# 74HC595.net
KiCad netlist of a schematic drawn in Altium Designer
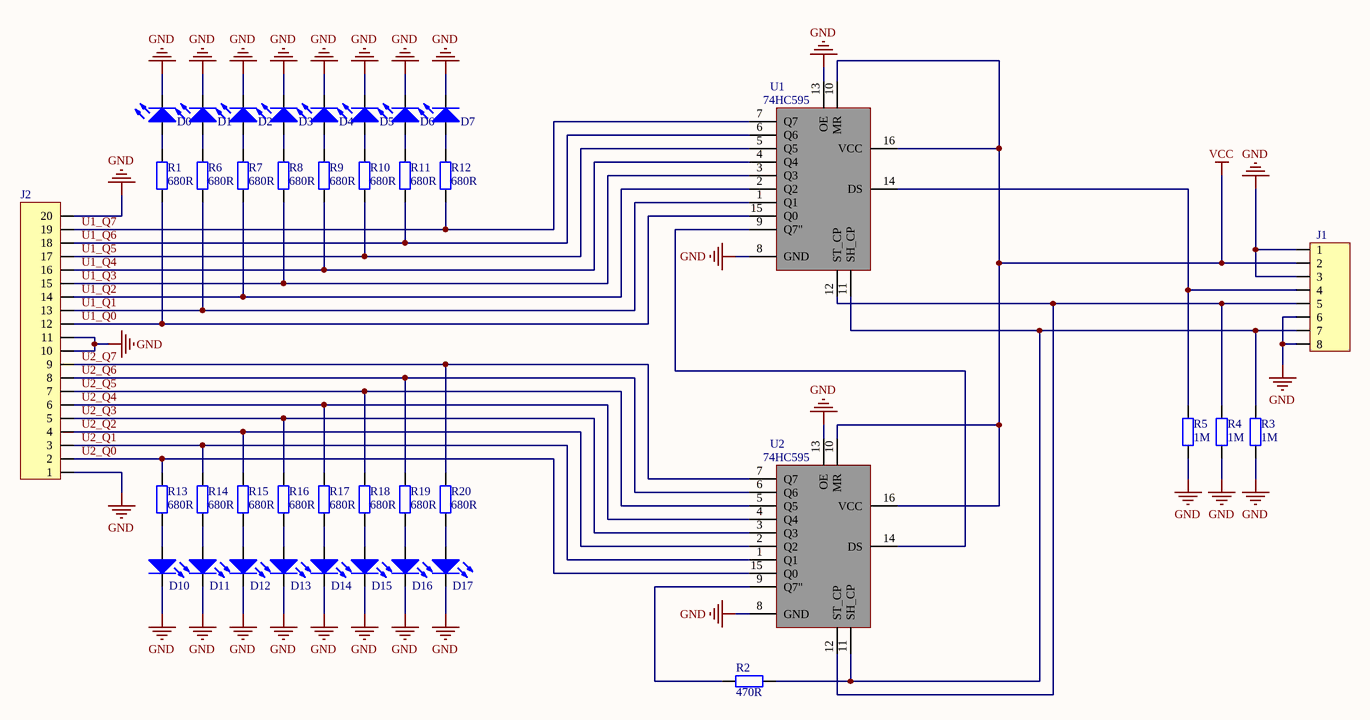
[diagram p0: 74HC595.SchDoc]

(export (version "E")
  (design (tool "Eeschema 10.0.6"))
  (components
    (comp (ref "D0")
      (value "LED0")
      (footprint "USER:1206LED")
      (description "LED灯")
      (fields (field (name "PUBLISHER") "Altium Limited"))
      (libsource (lib "USER") (part "LED0"))
    )
    (comp (ref "D1")
      (value "LED0")
      (footprint "USER:1206LED")
      (description "LED灯")
      (fields (field (name "PUBLISHER") "Altium Limited"))
      (libsource (lib "USER") (part "LED0"))
    )
    (comp (ref "D2")
      (value "LED0")
      (footprint "USER:1206LED")
      (description "LED灯")
      (fields (field (name "PUBLISHER") "Altium Limited"))
      (libsource (lib "USER") (part "LED0"))
    )
    (comp (ref "D3")
      (value "LED0")
      (footprint "USER:1206LED")
      (description "LED灯")
      (fields (field (name "PUBLISHER") "Altium Limited"))
      (libsource (lib "USER") (part "LED0"))
    )
    (comp (ref "D4")
      (value "LED0")
      (footprint "USER:1206LED")
      (description "LED灯")
      (fields (field (name "PUBLISHER") "Altium Limited"))
      (libsource (lib "USER") (part "LED0"))
    )
    (comp (ref "D5")
      (value "LED0")
      (footprint "USER:1206LED")
      (description "LED灯")
      (fields (field (name "PUBLISHER") "Altium Limited"))
      (libsource (lib "USER") (part "LED0"))
    )
    (comp (ref "D6")
      (value "LED0")
      (footprint "USER:1206LED")
      (description "LED灯")
      (fields (field (name "PUBLISHER") "Altium Limited"))
      (libsource (lib "USER") (part "LED0"))
    )
    (comp (ref "D7")
      (value "LED0")
      (footprint "USER:1206LED")
      (description "LED灯")
      (fields (field (name "PUBLISHER") "Altium Limited"))
      (libsource (lib "USER") (part "LED0"))
    )
    (comp (ref "D10")
      (value "LED0")
      (footprint "USER:1206LED")
      (description "LED灯")
      (fields (field (name "PUBLISHER") "Altium Limited"))
      (libsource (lib "USER") (part "LED0"))
    )
    (comp (ref "D11")
      (value "LED0")
      (footprint "USER:1206LED")
      (description "LED灯")
      (fields (field (name "PUBLISHER") "Altium Limited"))
      (libsource (lib "USER") (part "LED0"))
    )
    (comp (ref "D12")
      (value "LED0")
      (footprint "USER:1206LED")
      (description "LED灯")
      (fields (field (name "PUBLISHER") "Altium Limited"))
      (libsource (lib "USER") (part "LED0"))
    )
    (comp (ref "D13")
      (value "LED0")
      (footprint "USER:1206LED")
      (description "LED灯")
      (fields (field (name "PUBLISHER") "Altium Limited"))
      (libsource (lib "USER") (part "LED0"))
    )
    (comp (ref "D14")
      (value "LED0")
      (footprint "USER:1206LED")
      (description "LED灯")
      (fields (field (name "PUBLISHER") "Altium Limited"))
      (libsource (lib "USER") (part "LED0"))
    )
    (comp (ref "D15")
      (value "LED0")
      (footprint "USER:1206LED")
      (description "LED灯")
      (fields (field (name "PUBLISHER") "Altium Limited"))
      (libsource (lib "USER") (part "LED0"))
    )
    (comp (ref "D16")
      (value "LED0")
      (footprint "USER:1206LED")
      (description "LED灯")
      (fields (field (name "PUBLISHER") "Altium Limited"))
      (libsource (lib "USER") (part "LED0"))
    )
    (comp (ref "D17")
      (value "LED0")
      (footprint "USER:1206LED")
      (description "LED灯")
      (fields (field (name "PUBLISHER") "Altium Limited"))
      (libsource (lib "USER") (part "LED0"))
    )
    (comp (ref "J1")
      (value "Header8")
      (footprint "user:8P-2.54-H")
      (description "8PIN插座")
      (libsource (lib "USER") (part "Header8"))
    )
    (comp (ref "J2")
      (value "Header20")
      (footprint "USER:20P-2.54-H")
      (description "20PIN插座")
      (libsource (lib "USER") (part "Header20"))
    )
    (comp (ref "R1")
      (value "680R")
      (footprint "0805R_M")
      (description "电阻")
      (fields (field (name "PUBLISHER") "Altium Limited"))
      (libsource (lib "USER") (part "Res"))
    )
    (comp (ref "R2")
      (value "470R")
      (footprint "0805R_M")
      (description "电阻")
      (fields (field (name "PUBLISHER") "Altium Limited"))
      (libsource (lib "") (part "Res_1"))
    )
    (comp (ref "R3")
      (value "1M")
      (footprint "0805R_M")
      (description "电阻")
      (fields (field (name "PUBLISHER") "Altium Limited"))
      (libsource (lib "USER") (part "Res"))
    )
    (comp (ref "R4")
      (value "1M")
      (footprint "0805R_M")
      (description "电阻")
      (fields (field (name "PUBLISHER") "Altium Limited"))
      (libsource (lib "USER") (part "Res"))
    )
    (comp (ref "R5")
      (value "1M")
      (footprint "0805R_M")
      (description "电阻")
      (fields (field (name "PUBLISHER") "Altium Limited"))
      (libsource (lib "USER") (part "Res"))
    )
    (comp (ref "R6")
      (value "680R")
      (footprint "0805R_M")
      (description "电阻")
      (fields (field (name "PUBLISHER") "Altium Limited"))
      (libsource (lib "USER") (part "Res"))
    )
    (comp (ref "R7")
      (value "680R")
      (footprint "0805R_M")
      (description "电阻")
      (fields (field (name "PUBLISHER") "Altium Limited"))
      (libsource (lib "USER") (part "Res"))
    )
    (comp (ref "R8")
      (value "680R")
      (footprint "0805R_M")
      (description "电阻")
      (fields (field (name "PUBLISHER") "Altium Limited"))
      (libsource (lib "USER") (part "Res"))
    )
    (comp (ref "R9")
      (value "680R")
      (footprint "0805R_M")
      (description "电阻")
      (fields (field (name "PUBLISHER") "Altium Limited"))
      (libsource (lib "USER") (part "Res"))
    )
    (comp (ref "R10")
      (value "680R")
      (footprint "0805R_M")
      (description "电阻")
      (fields (field (name "PUBLISHER") "Altium Limited"))
      (libsource (lib "USER") (part "Res"))
    )
    (comp (ref "R11")
      (value "680R")
      (footprint "0805R_M")
      (description "电阻")
      (fields (field (name "PUBLISHER") "Altium Limited"))
      (libsource (lib "USER") (part "Res"))
    )
    (comp (ref "R12")
      (value "680R")
      (footprint "0805R_M")
      (description "电阻")
      (fields (field (name "PUBLISHER") "Altium Limited"))
      (libsource (lib "USER") (part "Res"))
    )
    (comp (ref "R13")
      (value "680R")
      (footprint "0805R_M")
      (description "电阻")
      (fields (field (name "PUBLISHER") "Altium Limited"))
      (libsource (lib "USER") (part "Res"))
    )
    (comp (ref "R14")
      (value "680R")
      (footprint "0805R_M")
      (description "电阻")
      (fields (field (name "PUBLISHER") "Altium Limited"))
      (libsource (lib "USER") (part "Res"))
    )
    (comp (ref "R15")
      (value "680R")
      (footprint "0805R_M")
      (description "电阻")
      (fields (field (name "PUBLISHER") "Altium Limited"))
      (libsource (lib "USER") (part "Res"))
    )
    (comp (ref "R16")
      (value "680R")
      (footprint "0805R_M")
      (description "电阻")
      (fields (field (name "PUBLISHER") "Altium Limited"))
      (libsource (lib "USER") (part "Res"))
    )
    (comp (ref "R17")
      (value "680R")
      (footprint "0805R_M")
      (description "电阻")
      (fields (field (name "PUBLISHER") "Altium Limited"))
      (libsource (lib "USER") (part "Res"))
    )
    (comp (ref "R18")
      (value "680R")
      (footprint "0805R_M")
      (description "电阻")
      (fields (field (name "PUBLISHER") "Altium Limited"))
      (libsource (lib "USER") (part "Res"))
    )
    (comp (ref "R19")
      (value "680R")
      (footprint "0805R_M")
      (description "电阻")
      (fields (field (name "PUBLISHER") "Altium Limited"))
      (libsource (lib "USER") (part "Res"))
    )
    (comp (ref "R20")
      (value "680R")
      (footprint "0805R_M")
      (description "电阻")
      (fields (field (name "PUBLISHER") "Altium Limited"))
      (libsource (lib "USER") (part "Res"))
    )
    (comp (ref "U1")
      (value "74HC595")
      (footprint "user1:SOIC-16_150mil")
      (description "移位寄存器")
      (libsource (lib "GUEST") (part "74LS595"))
    )
    (comp (ref "U2")
      (value "74HC595")
      (footprint "user1:SOIC-16_150mil")
      (description "移位寄存器")
      (libsource (lib "GUEST") (part "74LS595"))
    )
  )
  (nets
    (net (code "1") (name "/U1_Q0") (class "Default")
      (node (ref "J2") (pin "12") (pinfunction "12_12") (pintype "passive"))
      (node (ref "R1") (pin "2") (pinfunction "2_2") (pintype "passive"))
      (node (ref "U1") (pin "15") (pinfunction "Q0_15") (pintype "passive"))
    )
    (net (code "2") (name "/U1_Q1") (class "Default")
      (node (ref "J2") (pin "13") (pinfunction "13_13") (pintype "passive"))
      (node (ref "R6") (pin "2") (pinfunction "2_2") (pintype "passive"))
      (node (ref "U1") (pin "1") (pinfunction "Q1_1") (pintype "passive"))
    )
    (net (code "3") (name "/U1_Q2") (class "Default")
      (node (ref "J2") (pin "14") (pinfunction "14_14") (pintype "passive"))
      (node (ref "R7") (pin "2") (pinfunction "2_2") (pintype "passive"))
      (node (ref "U1") (pin "2") (pinfunction "Q2_2") (pintype "passive"))
    )
    (net (code "4") (name "/U1_Q3") (class "Default")
      (node (ref "J2") (pin "15") (pinfunction "15_15") (pintype "passive"))
      (node (ref "R8") (pin "2") (pinfunction "2_2") (pintype "passive"))
      (node (ref "U1") (pin "3") (pinfunction "Q3_3") (pintype "passive"))
    )
    (net (code "5") (name "/U1_Q4") (class "Default")
      (node (ref "J2") (pin "16") (pinfunction "16_16") (pintype "passive"))
      (node (ref "R9") (pin "2") (pinfunction "2_2") (pintype "passive"))
      (node (ref "U1") (pin "4") (pinfunction "Q4_4") (pintype "passive"))
    )
    (net (code "6") (name "/U1_Q5") (class "Default")
      (node (ref "J2") (pin "17") (pinfunction "17_17") (pintype "passive"))
      (node (ref "R10") (pin "2") (pinfunction "2_2") (pintype "passive"))
      (node (ref "U1") (pin "5") (pinfunction "Q5_5") (pintype "passive"))
    )
    (net (code "7") (name "/U1_Q6") (class "Default")
      (node (ref "J2") (pin "18") (pinfunction "18_18") (pintype "passive"))
      (node (ref "R11") (pin "2") (pinfunction "2_2") (pintype "passive"))
      (node (ref "U1") (pin "6") (pinfunction "Q6_6") (pintype "passive"))
    )
    (net (code "8") (name "/U1_Q7") (class "Default")
      (node (ref "J2") (pin "19") (pinfunction "19_19") (pintype "passive"))
      (node (ref "R12") (pin "2") (pinfunction "2_2") (pintype "passive"))
      (node (ref "U1") (pin "7") (pinfunction "Q7_7") (pintype "passive"))
    )
    (net (code "9") (name "/U2_Q0") (class "Default")
      (node (ref "J2") (pin "2") (pinfunction "2_2") (pintype "passive"))
      (node (ref "R13") (pin "1") (pinfunction "1_1") (pintype "passive"))
      (node (ref "U2") (pin "15") (pinfunction "Q0_15") (pintype "passive"))
    )
    (net (code "10") (name "/U2_Q1") (class "Default")
      (node (ref "J2") (pin "3") (pinfunction "3_3") (pintype "passive"))
      (node (ref "R14") (pin "1") (pinfunction "1_1") (pintype "passive"))
      (node (ref "U2") (pin "1") (pinfunction "Q1_1") (pintype "passive"))
    )
    (net (code "11") (name "/U2_Q2") (class "Default")
      (node (ref "J2") (pin "4") (pinfunction "4_4") (pintype "passive"))
      (node (ref "R15") (pin "1") (pinfunction "1_1") (pintype "passive"))
      (node (ref "U2") (pin "2") (pinfunction "Q2_2") (pintype "passive"))
    )
    (net (code "12") (name "/U2_Q3") (class "Default")
      (node (ref "J2") (pin "5") (pinfunction "5_5") (pintype "passive"))
      (node (ref "R16") (pin "1") (pinfunction "1_1") (pintype "passive"))
      (node (ref "U2") (pin "3") (pinfunction "Q3_3") (pintype "passive"))
    )
    (net (code "13") (name "/U2_Q4") (class "Default")
      (node (ref "J2") (pin "6") (pinfunction "6_6") (pintype "passive"))
      (node (ref "R17") (pin "1") (pinfunction "1_1") (pintype "passive"))
      (node (ref "U2") (pin "4") (pinfunction "Q4_4") (pintype "passive"))
    )
    (net (code "14") (name "/U2_Q5") (class "Default")
      (node (ref "J2") (pin "7") (pinfunction "7_7") (pintype "passive"))
      (node (ref "R18") (pin "1") (pinfunction "1_1") (pintype "passive"))
      (node (ref "U2") (pin "5") (pinfunction "Q5_5") (pintype "passive"))
    )
    (net (code "15") (name "/U2_Q6") (class "Default")
      (node (ref "J2") (pin "8") (pinfunction "8_8") (pintype "passive"))
      (node (ref "R19") (pin "1") (pinfunction "1_1") (pintype "passive"))
      (node (ref "U2") (pin "6") (pinfunction "Q6_6") (pintype "passive"))
    )
    (net (code "16") (name "/U2_Q7") (class "Default")
      (node (ref "J2") (pin "9") (pinfunction "9_9") (pintype "passive"))
      (node (ref "R20") (pin "1") (pinfunction "1_1") (pintype "passive"))
      (node (ref "U2") (pin "7") (pinfunction "Q7_7") (pintype "passive"))
    )
    (net (code "17") (name "GND") (class "Default")
      (node (ref "D0") (pin "2") (pinfunction "K_2") (pintype "passive"))
      (node (ref "D1") (pin "2") (pinfunction "K_2") (pintype "passive"))
      (node (ref "D10") (pin "2") (pinfunction "K_2") (pintype "passive"))
      (node (ref "D11") (pin "2") (pinfunction "K_2") (pintype "passive"))
      (node (ref "D12") (pin "2") (pinfunction "K_2") (pintype "passive"))
      (node (ref "D13") (pin "2") (pinfunction "K_2") (pintype "passive"))
      (node (ref "D14") (pin "2") (pinfunction "K_2") (pintype "passive"))
      (node (ref "D15") (pin "2") (pinfunction "K_2") (pintype "passive"))
      (node (ref "D16") (pin "2") (pinfunction "K_2") (pintype "passive"))
      (node (ref "D17") (pin "2") (pinfunction "K_2") (pintype "passive"))
      (node (ref "D2") (pin "2") (pinfunction "K_2") (pintype "passive"))
      (node (ref "D3") (pin "2") (pinfunction "K_2") (pintype "passive"))
      (node (ref "D4") (pin "2") (pinfunction "K_2") (pintype "passive"))
      (node (ref "D5") (pin "2") (pinfunction "K_2") (pintype "passive"))
      (node (ref "D6") (pin "2") (pinfunction "K_2") (pintype "passive"))
      (node (ref "D7") (pin "2") (pinfunction "K_2") (pintype "passive"))
      (node (ref "J1") (pin "1") (pinfunction "1_1") (pintype "passive"))
      (node (ref "J1") (pin "3") (pinfunction "3_3") (pintype "passive"))
      (node (ref "J1") (pin "6") (pinfunction "6_6") (pintype "passive"))
      (node (ref "J1") (pin "8") (pinfunction "8_8") (pintype "passive"))
      (node (ref "J2") (pin "1") (pinfunction "1_1") (pintype "passive"))
      (node (ref "J2") (pin "10") (pinfunction "10_10") (pintype "passive"))
      (node (ref "J2") (pin "11") (pinfunction "11_11") (pintype "passive"))
      (node (ref "J2") (pin "20") (pinfunction "20_20") (pintype "passive"))
      (node (ref "R3") (pin "2") (pinfunction "2_2") (pintype "passive"))
      (node (ref "R4") (pin "2") (pinfunction "2_2") (pintype "passive"))
      (node (ref "R5") (pin "2") (pinfunction "2_2") (pintype "passive"))
      (node (ref "U1") (pin "13") (pinfunction "OE_13") (pintype "passive"))
      (node (ref "U1") (pin "8") (pinfunction "GND_8") (pintype "passive"))
      (node (ref "U2") (pin "13") (pinfunction "OE_13") (pintype "passive"))
      (node (ref "U2") (pin "8") (pinfunction "GND_8") (pintype "passive"))
    )
    (net (code "18") (name "Net-(D0-A)") (class "Default")
      (node (ref "D0") (pin "1") (pinfunction "A_1") (pintype "passive"))
      (node (ref "R1") (pin "1") (pinfunction "1_1") (pintype "passive"))
    )
    (net (code "19") (name "Net-(D1-A)") (class "Default")
      (node (ref "D1") (pin "1") (pinfunction "A_1") (pintype "passive"))
      (node (ref "R6") (pin "1") (pinfunction "1_1") (pintype "passive"))
    )
    (net (code "20") (name "Net-(D2-A)") (class "Default")
      (node (ref "D2") (pin "1") (pinfunction "A_1") (pintype "passive"))
      (node (ref "R7") (pin "1") (pinfunction "1_1") (pintype "passive"))
    )
    (net (code "21") (name "Net-(D3-A)") (class "Default")
      (node (ref "D3") (pin "1") (pinfunction "A_1") (pintype "passive"))
      (node (ref "R8") (pin "1") (pinfunction "1_1") (pintype "passive"))
    )
    (net (code "22") (name "Net-(D4-A)") (class "Default")
      (node (ref "D4") (pin "1") (pinfunction "A_1") (pintype "passive"))
      (node (ref "R9") (pin "1") (pinfunction "1_1") (pintype "passive"))
    )
    (net (code "23") (name "Net-(D5-A)") (class "Default")
      (node (ref "D5") (pin "1") (pinfunction "A_1") (pintype "passive"))
      (node (ref "R10") (pin "1") (pinfunction "1_1") (pintype "passive"))
    )
    (net (code "24") (name "Net-(D6-A)") (class "Default")
      (node (ref "D6") (pin "1") (pinfunction "A_1") (pintype "passive"))
      (node (ref "R11") (pin "1") (pinfunction "1_1") (pintype "passive"))
    )
    (net (code "25") (name "Net-(D7-A)") (class "Default")
      (node (ref "D7") (pin "1") (pinfunction "A_1") (pintype "passive"))
      (node (ref "R12") (pin "1") (pinfunction "1_1") (pintype "passive"))
    )
    (net (code "26") (name "Net-(D10-A)") (class "Default")
      (node (ref "D10") (pin "1") (pinfunction "A_1") (pintype "passive"))
      (node (ref "R13") (pin "2") (pinfunction "2_2") (pintype "passive"))
    )
    (net (code "27") (name "Net-(D11-A)") (class "Default")
      (node (ref "D11") (pin "1") (pinfunction "A_1") (pintype "passive"))
      (node (ref "R14") (pin "2") (pinfunction "2_2") (pintype "passive"))
    )
    (net (code "28") (name "Net-(D12-A)") (class "Default")
      (node (ref "D12") (pin "1") (pinfunction "A_1") (pintype "passive"))
      (node (ref "R15") (pin "2") (pinfunction "2_2") (pintype "passive"))
    )
    (net (code "29") (name "Net-(D13-A)") (class "Default")
      (node (ref "D13") (pin "1") (pinfunction "A_1") (pintype "passive"))
      (node (ref "R16") (pin "2") (pinfunction "2_2") (pintype "passive"))
    )
    (net (code "30") (name "Net-(D14-A)") (class "Default")
      (node (ref "D14") (pin "1") (pinfunction "A_1") (pintype "passive"))
      (node (ref "R17") (pin "2") (pinfunction "2_2") (pintype "passive"))
    )
    (net (code "31") (name "Net-(D15-A)") (class "Default")
      (node (ref "D15") (pin "1") (pinfunction "A_1") (pintype "passive"))
      (node (ref "R18") (pin "2") (pinfunction "2_2") (pintype "passive"))
    )
    (net (code "32") (name "Net-(D16-A)") (class "Default")
      (node (ref "D16") (pin "1") (pinfunction "A_1") (pintype "passive"))
      (node (ref "R19") (pin "2") (pinfunction "2_2") (pintype "passive"))
    )
    (net (code "33") (name "Net-(D17-A)") (class "Default")
      (node (ref "D17") (pin "1") (pinfunction "A_1") (pintype "passive"))
      (node (ref "R20") (pin "2") (pinfunction "2_2") (pintype "passive"))
    )
    (net (code "34") (name "Net-(U1-DS)") (class "Default")
      (node (ref "J1") (pin "4") (pinfunction "4_4") (pintype "passive"))
      (node (ref "R5") (pin "1") (pinfunction "1_1") (pintype "passive"))
      (node (ref "U1") (pin "14") (pinfunction "DS_14") (pintype "passive"))
    )
    (net (code "35") (name "Net-(U1-Q7\")") (class "Default")
      (node (ref "U1") (pin "9") (pinfunction "Q7\"_9") (pintype "passive"))
      (node (ref "U2") (pin "14") (pinfunction "DS_14") (pintype "passive"))
    )
    (net (code "36") (name "Net-(U1-SH_CP)") (class "Default")
      (node (ref "J1") (pin "7") (pinfunction "7_7") (pintype "passive"))
      (node (ref "R2") (pin "2") (pinfunction "2_2") (pintype "passive"))
      (node (ref "R3") (pin "1") (pinfunction "1_1") (pintype "passive"))
      (node (ref "U1") (pin "11") (pinfunction "SH_CP_11") (pintype "passive"))
      (node (ref "U2") (pin "11") (pinfunction "SH_CP_11") (pintype "passive"))
    )
    (net (code "37") (name "Net-(U1-ST_CP)") (class "Default")
      (node (ref "J1") (pin "5") (pinfunction "5_5") (pintype "passive"))
      (node (ref "R4") (pin "1") (pinfunction "1_1") (pintype "passive"))
      (node (ref "U1") (pin "12") (pinfunction "ST_CP_12") (pintype "passive"))
      (node (ref "U2") (pin "12") (pinfunction "ST_CP_12") (pintype "passive"))
    )
    (net (code "38") (name "Net-(U2-Q7\")") (class "Default")
      (node (ref "R2") (pin "1") (pinfunction "1_1") (pintype "passive"))
      (node (ref "U2") (pin "9") (pinfunction "Q7\"_9") (pintype "passive"))
    )
    (net (code "39") (name "VCC") (class "Default")
      (node (ref "J1") (pin "2") (pinfunction "2_2") (pintype "passive"))
      (node (ref "U1") (pin "10") (pinfunction "MR_10") (pintype "passive"))
      (node (ref "U1") (pin "16") (pinfunction "VCC_16") (pintype "passive"))
      (node (ref "U2") (pin "10") (pinfunction "MR_10") (pintype "passive"))
      (node (ref "U2") (pin "16") (pinfunction "VCC_16") (pintype "passive"))
    )
  )
)
